# 5V_Regulator.net
KiCad netlist of a schematic drawn in Altium Designer
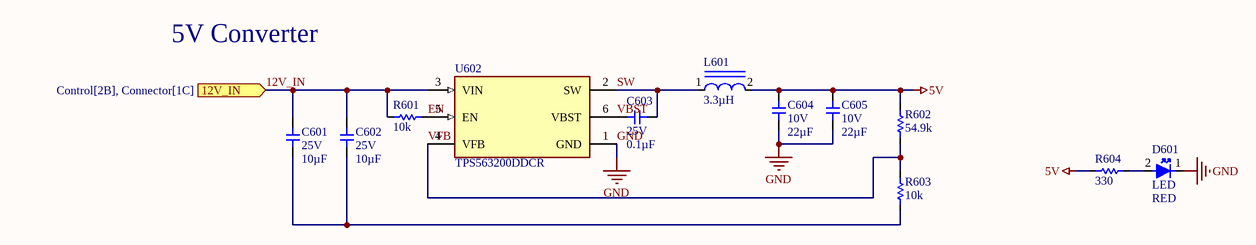
[diagram p0: 5V_Regulator.SchDoc]

(export (version "E")
  (design (tool "Eeschema 10.0.6"))
  (components
    (comp (ref "C601")
      (value "non-polar_Capacitor")
      (footprint "0805")
      (description "SMD type ceramic capacitor")
      (fields
        (field (name "VOLTAGE") "25V")
        (field (name "CAPACITANCE") "10µF")
        (field (name "SOURCE") "robit_passive.SchLib")
      )
      (libsource (lib "robit circuit") (part "Capacitor"))
    )
    (comp (ref "C602")
      (value "non-polar_Capacitor")
      (footprint "0805")
      (description "SMD type ceramic capacitor")
      (fields
        (field (name "VOLTAGE") "25V")
        (field (name "CAPACITANCE") "10µF")
        (field (name "SOURCE") "robit_passive.SchLib")
      )
      (libsource (lib "robit circuit") (part "Capacitor"))
    )
    (comp (ref "C603")
      (value "non-polar_Capacitor")
      (footprint "0805")
      (description "SMD type ceramic capacitor")
      (fields
        (field (name "VOLTAGE") "25V")
        (field (name "CAPACITANCE") "0.1µF")
        (field (name "SOURCE") "robit_passive.SchLib")
      )
      (libsource (lib "robit circuit") (part "Capacitor"))
    )
    (comp (ref "C604")
      (value "non-polar_Capacitor")
      (footprint "0805")
      (description "SMD type ceramic capacitor")
      (fields
        (field (name "VOLTAGE") "10V")
        (field (name "CAPACITANCE") "22µF")
        (field (name "SOURCE") "robit_passive.SchLib")
      )
      (libsource (lib "robit circuit") (part "Capacitor"))
    )
    (comp (ref "C605")
      (value "non-polar_Capacitor")
      (footprint "0805")
      (description "SMD type ceramic capacitor")
      (fields
        (field (name "VOLTAGE") "10V")
        (field (name "CAPACITANCE") "22µF")
        (field (name "SOURCE") "robit_passive.SchLib")
      )
      (libsource (lib "robit circuit") (part "Capacitor"))
    )
    (comp (ref "D601")
      (value "LED")
      (footprint "SMD_LED")
      (description "Light Emitting Diode")
      (fields (field (name "COLOR") "RED") (field (name "SOURCE") "robit_passive.SchLib"))
      (libsource (lib "robit circuit") (part "LED"))
    )
    (comp (ref "L601")
      (value "inductor_SRP7030CA")
      (footprint "FP-SRP7030CA-MFG")
      (description "General Purpose Inductor, 6.8uH, 20%, 1 Element, Powdered Metal Alloy-Core, SMD, 3130")
      (fields (field (name "INDUCTANCE") "3.3µH"))
      (libsource (lib "robit circuit") (part "c15dd3e3c879a918231412629381336"))
    )
    (comp (ref "R601")
      (value "Resistor")
      (footprint "0805")
      (description "SMD type resistor")
      (fields (field (name "RESISTANCE") "10k") (field (name "SOURCE") "robit_passive.SchLib"))
      (libsource (lib "robit circuit") (part "Resistor"))
    )
    (comp (ref "R602")
      (value "Resistor")
      (footprint "0805")
      (description "SMD type resistor")
      (fields (field (name "RESISTANCE") "54.9k") (field (name "SOURCE") "robit_passive.SchLib"))
      (libsource (lib "robit circuit") (part "Resistor"))
    )
    (comp (ref "R603")
      (value "Resistor")
      (footprint "0805")
      (description "SMD type resistor")
      (fields (field (name "RESISTANCE") "10k") (field (name "SOURCE") "robit_passive.SchLib"))
      (libsource (lib "robit circuit") (part "Resistor"))
    )
    (comp (ref "R604")
      (value "Resistor")
      (footprint "SMD_Resistor")
      (description "SMD type resistor")
      (fields (field (name "RESISTANCE") "330") (field (name "SOURCE") "robit_passive.SchLib"))
      (libsource (lib "") (part "Resistor_1"))
    )
    (comp (ref "U602")
      (value "TPS563200DDCR")
      (footprint "FP-DDC0006A-MFG")
      (description "IC REG BUCK ADJ 3A TSOT23-6")
      (libsource (lib "Altium Content Vault") (part "31d0a13bcb823f7fa58c78a9b473f81"))
    )
  )
  (nets
    (net (code "1") (name "/12V_IN") (class "Default")
      (node (ref "C601") (pin "2") (pinfunction "2_2") (pintype "passive"))
      (node (ref "C602") (pin "2") (pinfunction "2_2") (pintype "passive"))
      (node (ref "R601") (pin "1") (pinfunction "1_1") (pintype "passive"))
      (node (ref "U602") (pin "3") (pinfunction "VIN_3") (pintype "input"))
    )
    (net (code "2") (name "/EN") (class "Default")
      (node (ref "R601") (pin "2") (pinfunction "2_2") (pintype "passive"))
      (node (ref "U602") (pin "5") (pinfunction "EN_5") (pintype "input"))
    )
    (net (code "3") (name "/SW") (class "Default")
      (node (ref "C603") (pin "2") (pinfunction "2_2") (pintype "passive"))
      (node (ref "L601") (pin "1") (pinfunction "1_1") (pintype "passive"))
      (node (ref "U602") (pin "2") (pinfunction "SW_2") (pintype "passive"))
    )
    (net (code "4") (name "/VBST") (class "Default")
      (node (ref "C603") (pin "1") (pinfunction "1_1") (pintype "passive"))
      (node (ref "U602") (pin "6") (pinfunction "VBST_6") (pintype "passive"))
    )
    (net (code "5") (name "/VFB") (class "Default")
      (node (ref "R602") (pin "1") (pinfunction "1_1") (pintype "passive"))
      (node (ref "R603") (pin "2") (pinfunction "2_2") (pintype "passive"))
      (node (ref "U602") (pin "4") (pinfunction "VFB_4") (pintype "passive"))
    )
    (net (code "6") (name "5V") (class "Default")
      (node (ref "C604") (pin "2") (pinfunction "2_2") (pintype "passive"))
      (node (ref "C605") (pin "2") (pinfunction "2_2") (pintype "passive"))
      (node (ref "L601") (pin "2") (pinfunction "2_2") (pintype "passive"))
      (node (ref "R602") (pin "2") (pinfunction "2_2") (pintype "passive"))
      (node (ref "R604") (pin "1") (pintype "passive"))
    )
    (net (code "7") (name "GND") (class "Default")
      (node (ref "C604") (pin "1") (pinfunction "1_1") (pintype "passive"))
      (node (ref "C605") (pin "1") (pinfunction "1_1") (pintype "passive"))
      (node (ref "D601") (pin "1") (pintype "passive"))
      (node (ref "U602") (pin "1") (pinfunction "GND_1") (pintype "power_in"))
    )
    (net (code "8") (name "Net-(C601-Pad1)") (class "Default")
      (node (ref "C601") (pin "1") (pinfunction "1_1") (pintype "passive"))
      (node (ref "C602") (pin "1") (pinfunction "1_1") (pintype "passive"))
      (node (ref "R603") (pin "1") (pinfunction "1_1") (pintype "passive"))
    )
    (net (code "9") (name "Net-(D601-Pad2)") (class "Default")
      (node (ref "D601") (pin "2") (pintype "passive"))
      (node (ref "R604") (pin "2") (pintype "passive"))
    )
  )
)
